# REVERSE_POLARITY_PROT.net
KiCad netlist of a schematic drawn in Altium Designer
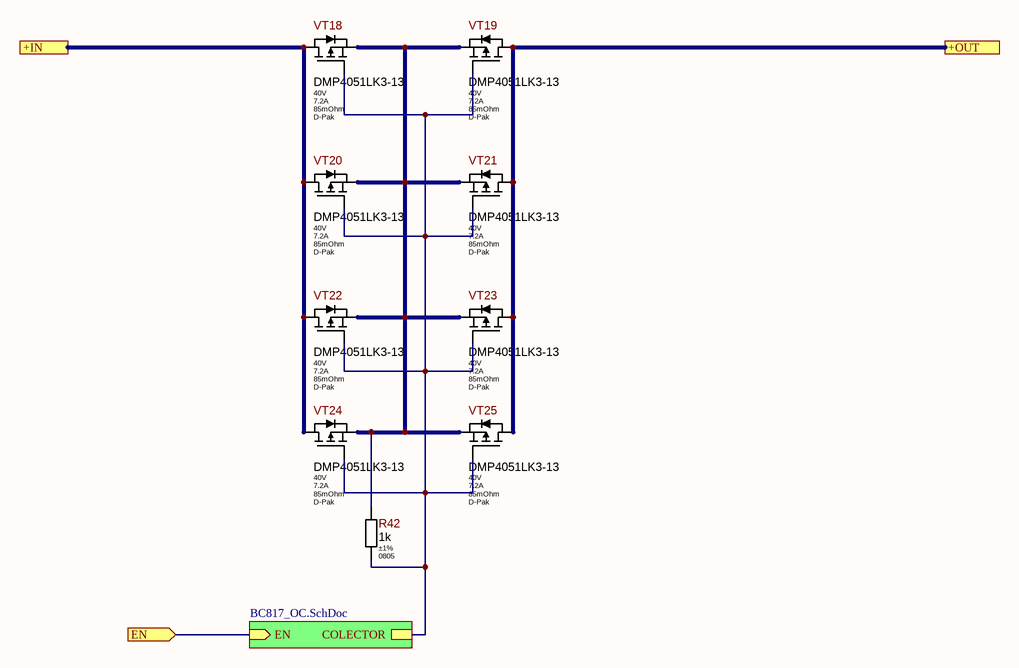
[diagram p0: REVERSE_POLARITY_PROT.SchDoc]

(export (version "E")
  (design (tool "Eeschema 10.0.6"))
  (components
    (comp (ref "R42")
      (value "1k")
      (footprint "R_ANY_CHIP_0805_MED")
      (description "1 kOhms ±1%, 1/8W 0805 Thick Film Resistor")
      (fields
        (field (name "TOLERANCE") "±1%")
        (field (name "PACKAGE") "0805")
        (field (name "PART NUMBER") "RC0805FR-071KL")
        (field (name "MANUFACTURER") "Yageo")
      )
      (libsource (lib "resistors") (part "RC0805FR-071KL"))
    )
    (comp (ref "VT18")
      (value "DMP4051LK3-13")
      (footprint "DPAK_REC")
      (description "-40V, -7.2A max P-Channel Enhancement MOSFET, 59mOhm @ Vgs = -4.5V")
      (fields
        (field (name "PART NUMBER") "DMP4051LK3-13")
        (field (name "VDS") "40V")
        (field (name "ID") "7.2A")
        (field (name "RDS") "85mOhm")
        (field (name "PACKAGE") "D-Pak")
        (field (name "MANUFACTURER") "Diodes Incorporated")
      )
      (libsource (lib "transistors") (part "DMP4051LK3-13"))
    )
    (comp (ref "VT19")
      (value "DMP4051LK3-13")
      (footprint "DPAK_REC")
      (description "-40V, -7.2A max P-Channel Enhancement MOSFET, 59mOhm @ Vgs = -4.5V")
      (fields
        (field (name "PART NUMBER") "DMP4051LK3-13")
        (field (name "VDS") "40V")
        (field (name "ID") "7.2A")
        (field (name "RDS") "85mOhm")
        (field (name "PACKAGE") "D-Pak")
        (field (name "MANUFACTURER") "Diodes Incorporated")
      )
      (libsource (lib "transistors") (part "DMP4051LK3-13"))
    )
    (comp (ref "VT20")
      (value "DMP4051LK3-13")
      (footprint "DPAK_REC")
      (description "-40V, -7.2A max P-Channel Enhancement MOSFET, 59mOhm @ Vgs = -4.5V")
      (fields
        (field (name "PART NUMBER") "DMP4051LK3-13")
        (field (name "VDS") "40V")
        (field (name "ID") "7.2A")
        (field (name "RDS") "85mOhm")
        (field (name "PACKAGE") "D-Pak")
        (field (name "MANUFACTURER") "Diodes Incorporated")
      )
      (libsource (lib "transistors") (part "DMP4051LK3-13"))
    )
    (comp (ref "VT21")
      (value "DMP4051LK3-13")
      (footprint "DPAK_REC")
      (description "-40V, -7.2A max P-Channel Enhancement MOSFET, 59mOhm @ Vgs = -4.5V")
      (fields
        (field (name "PART NUMBER") "DMP4051LK3-13")
        (field (name "VDS") "40V")
        (field (name "ID") "7.2A")
        (field (name "RDS") "85mOhm")
        (field (name "PACKAGE") "D-Pak")
        (field (name "MANUFACTURER") "Diodes Incorporated")
      )
      (libsource (lib "transistors") (part "DMP4051LK3-13"))
    )
    (comp (ref "VT22")
      (value "DMP4051LK3-13")
      (footprint "DPAK_REC")
      (description "-40V, -7.2A max P-Channel Enhancement MOSFET, 59mOhm @ Vgs = -4.5V")
      (fields
        (field (name "PART NUMBER") "DMP4051LK3-13")
        (field (name "VDS") "40V")
        (field (name "ID") "7.2A")
        (field (name "RDS") "85mOhm")
        (field (name "PACKAGE") "D-Pak")
        (field (name "MANUFACTURER") "Diodes Incorporated")
      )
      (libsource (lib "transistors") (part "DMP4051LK3-13"))
    )
    (comp (ref "VT23")
      (value "DMP4051LK3-13")
      (footprint "DPAK_REC")
      (description "-40V, -7.2A max P-Channel Enhancement MOSFET, 59mOhm @ Vgs = -4.5V")
      (fields
        (field (name "PART NUMBER") "DMP4051LK3-13")
        (field (name "VDS") "40V")
        (field (name "ID") "7.2A")
        (field (name "RDS") "85mOhm")
        (field (name "PACKAGE") "D-Pak")
        (field (name "MANUFACTURER") "Diodes Incorporated")
      )
      (libsource (lib "transistors") (part "DMP4051LK3-13"))
    )
    (comp (ref "VT24")
      (value "DMP4051LK3-13")
      (footprint "DPAK_REC")
      (description "-40V, -7.2A max P-Channel Enhancement MOSFET, 59mOhm @ Vgs = -4.5V")
      (fields
        (field (name "PART NUMBER") "DMP4051LK3-13")
        (field (name "VDS") "40V")
        (field (name "ID") "7.2A")
        (field (name "RDS") "85mOhm")
        (field (name "PACKAGE") "D-Pak")
        (field (name "MANUFACTURER") "Diodes Incorporated")
      )
      (libsource (lib "transistors") (part "DMP4051LK3-13"))
    )
    (comp (ref "VT25")
      (value "DMP4051LK3-13")
      (footprint "DPAK_REC")
      (description "-40V, -7.2A max P-Channel Enhancement MOSFET, 59mOhm @ Vgs = -4.5V")
      (fields
        (field (name "PART NUMBER") "DMP4051LK3-13")
        (field (name "VDS") "40V")
        (field (name "ID") "7.2A")
        (field (name "RDS") "85mOhm")
        (field (name "PACKAGE") "D-Pak")
        (field (name "MANUFACTURER") "Diodes Incorporated")
      )
      (libsource (lib "transistors") (part "DMP4051LK3-13"))
    )
  )
  (nets
    (net (code "1") (name "/+IN") (class "Default")
      (node (ref "VT18") (pin "2") (pinfunction "D_2") (pintype "passive"))
      (node (ref "VT20") (pin "2") (pinfunction "D_2") (pintype "passive"))
      (node (ref "VT22") (pin "2") (pinfunction "D_2") (pintype "passive"))
      (node (ref "VT24") (pin "2") (pinfunction "D_2") (pintype "passive"))
    )
    (net (code "2") (name "/+OUT") (class "Default")
      (node (ref "VT19") (pin "2") (pinfunction "D_2") (pintype "passive"))
      (node (ref "VT21") (pin "2") (pinfunction "D_2") (pintype "passive"))
      (node (ref "VT23") (pin "2") (pinfunction "D_2") (pintype "passive"))
      (node (ref "VT25") (pin "2") (pinfunction "D_2") (pintype "passive"))
    )
    (net (code "3") (name "/COLECTOR") (class "Default")
      (node (ref "R42") (pin "1") (pintype "passive"))
      (node (ref "VT18") (pin "1") (pinfunction "G_1") (pintype "passive"))
      (node (ref "VT19") (pin "1") (pinfunction "G_1") (pintype "passive"))
      (node (ref "VT20") (pin "1") (pinfunction "G_1") (pintype "passive"))
      (node (ref "VT21") (pin "1") (pinfunction "G_1") (pintype "passive"))
      (node (ref "VT22") (pin "1") (pinfunction "G_1") (pintype "passive"))
      (node (ref "VT23") (pin "1") (pinfunction "G_1") (pintype "passive"))
      (node (ref "VT24") (pin "1") (pinfunction "G_1") (pintype "passive"))
      (node (ref "VT25") (pin "1") (pinfunction "G_1") (pintype "passive"))
    )
    (net (code "5") (name "Net-(VT18-S)") (class "Default")
      (node (ref "R42") (pin "2") (pintype "passive"))
      (node (ref "VT18") (pin "3") (pinfunction "S_3") (pintype "passive"))
      (node (ref "VT19") (pin "3") (pinfunction "S_3") (pintype "passive"))
      (node (ref "VT20") (pin "3") (pinfunction "S_3") (pintype "passive"))
      (node (ref "VT21") (pin "3") (pinfunction "S_3") (pintype "passive"))
      (node (ref "VT22") (pin "3") (pinfunction "S_3") (pintype "passive"))
      (node (ref "VT23") (pin "3") (pinfunction "S_3") (pintype "passive"))
      (node (ref "VT24") (pin "3") (pinfunction "S_3") (pintype "passive"))
      (node (ref "VT25") (pin "3") (pinfunction "S_3") (pintype "passive"))
    )
  )
)
